# JoystickWing.net
KiCad netlist of a schematic drawn in EAGLE
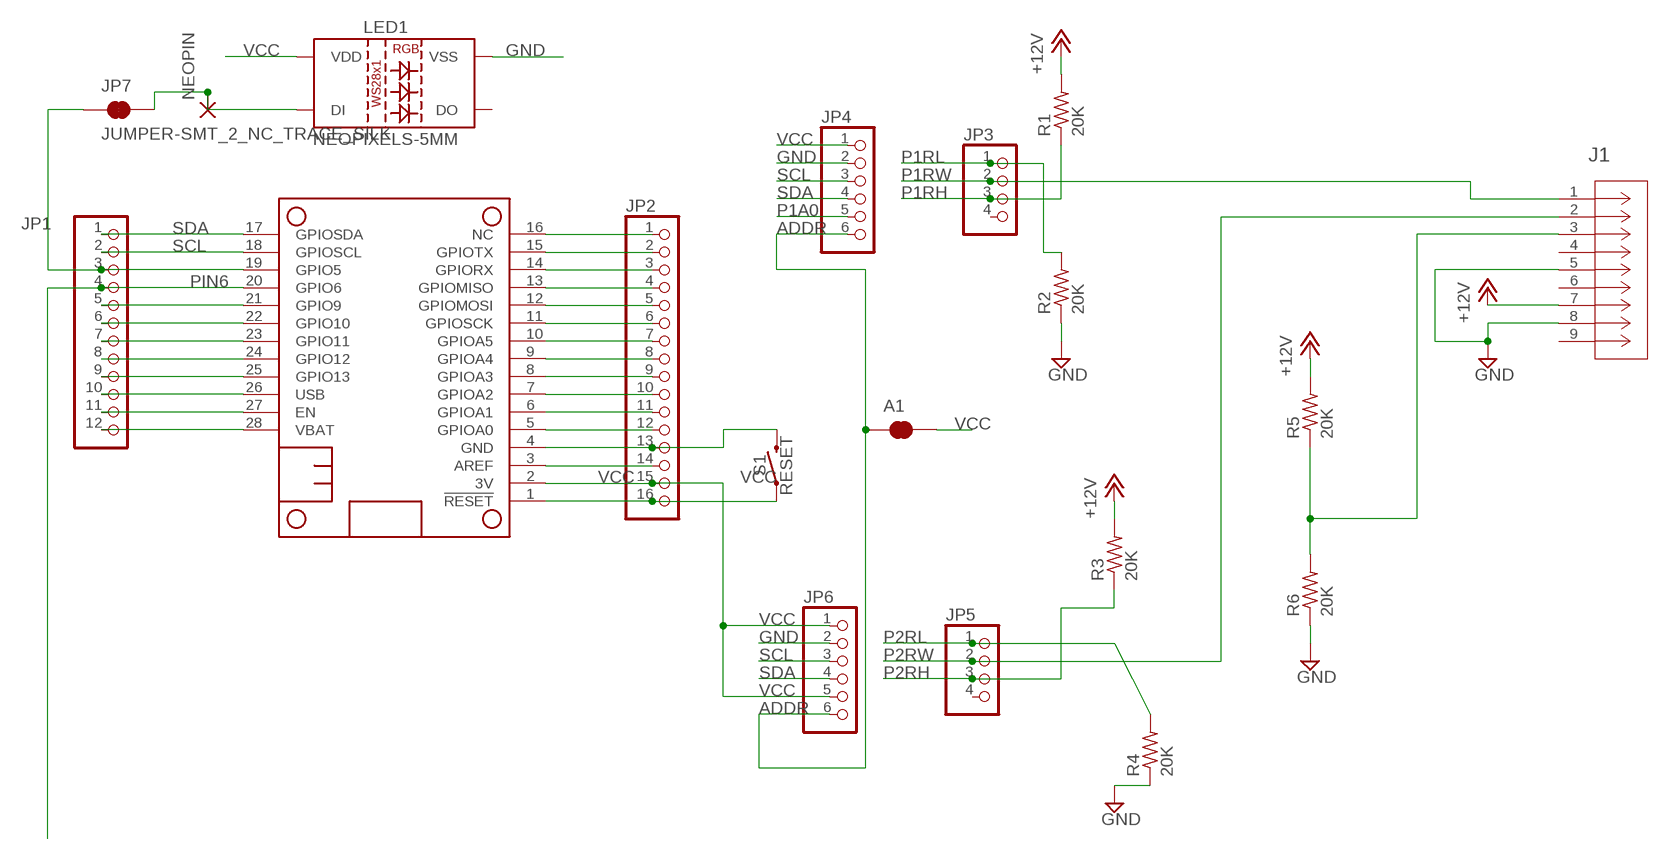
[diagram p0: schematic, sheet 1]

(export (version "E")
  (design (tool "Eeschema 10.0.6"))
  (components
    (comp (ref "A1")
      (value "JUMPER-SMT_2_NC_TRACE_SILK")
      (footprint "eagle-import:SMT-JUMPER_2_NC_TRACE_SILK")
      (libsource (lib "eagle-import") (part "JUMPER-SMT_2_NC_TRACE_SILK"))
    )
    (comp (ref "J1")
      (value "5747844-4")
      (footprint "eagle-import:CONN_5747844-4")
      (fields (field (name "MANUFACTURER_PART_NUMBER") "57478444"))
      (libsource (lib "eagle-import") (part "5747844-4"))
    )
    (comp (ref "JP1")
      (value "PINHD-1X12")
      (footprint "eagle-import:1X12")
      (libsource (lib "eagle-import") (part "PINHD-1X12"))
    )
    (comp (ref "JP2")
      (value "PINHD-1X16")
      (footprint "eagle-import:1X16")
      (libsource (lib "eagle-import") (part "PINHD-1X16"))
    )
    (comp (ref "JP3")
      (value "HEADER-1X4ROUND")
      (footprint "eagle-import:1X04_ROUND")
      (libsource (lib "eagle-import") (part "HEADER-1X4ROUND"))
    )
    (comp (ref "JP4")
      (value "HEADER-1X6ROUND")
      (footprint "eagle-import:1X06_ROUND")
      (libsource (lib "eagle-import") (part "HEADER-1X6ROUND"))
    )
    (comp (ref "JP5")
      (value "HEADER-1X4ROUND")
      (footprint "eagle-import:1X04_ROUND")
      (libsource (lib "eagle-import") (part "HEADER-1X4ROUND"))
    )
    (comp (ref "JP6")
      (value "HEADER-1X6ROUND")
      (footprint "eagle-import:1X06_ROUND")
      (libsource (lib "eagle-import") (part "HEADER-1X6ROUND"))
    )
    (comp (ref "JP7")
      (value "JUMPER-SMT_2_NC_TRACE_SILK")
      (footprint "eagle-import:SMT-JUMPER_2_NC_TRACE_SILK")
      (libsource (lib "eagle-import") (part "JUMPER-SMT_2_NC_TRACE_SILK"))
    )
    (comp (ref "LED1")
      (value "NEOPIXELS-5MM")
      (footprint "eagle-import:NEOPIXELS-5MM")
      (libsource (lib "eagle-import") (part "NEOPIXELS-5MM"))
    )
    (comp (ref "MS1")
      (value "FEATHERWING_NODIM")
      (footprint "eagle-import:FEATHERWING_DIM")
      (libsource (lib "eagle-import") (part "FEATHERWING_NODIM"))
    )
    (comp (ref "NEOPIN")
      (value "2,54/1,1")
      (footprint "eagle-import:2,54_1,1")
      (libsource (lib "eagle-import") (part "2,54/1,1"))
    )
    (comp (ref "R1")
      (value "20K")
      (footprint "eagle-import:0204_7")
      (libsource (lib "eagle-import") (part "R-US_0204/7"))
    )
    (comp (ref "R2")
      (value "20K")
      (footprint "eagle-import:0204_7")
      (libsource (lib "eagle-import") (part "R-US_0204/7"))
    )
    (comp (ref "R3")
      (value "20K")
      (footprint "eagle-import:0204_7")
      (libsource (lib "eagle-import") (part "R-US_0204/7"))
    )
    (comp (ref "R4")
      (value "20K")
      (footprint "eagle-import:0204_7")
      (libsource (lib "eagle-import") (part "R-US_0204/7"))
    )
    (comp (ref "R5")
      (value "20K")
      (footprint "eagle-import:0204_7")
      (libsource (lib "eagle-import") (part "R-US_0204/7"))
    )
    (comp (ref "R6")
      (value "20K")
      (footprint "eagle-import:0204_7")
      (libsource (lib "eagle-import") (part "R-US_0204/7"))
    )
    (comp (ref "S1")
      (value "RESET")
      (footprint "eagle-import:DTS-3")
      (libsource (lib "eagle-import") (part "SWITCH_DTS-3"))
    )
  )
  (nets
    (net (code "1") (name "+12V") (class "Default")
      (node (ref "J1") (pin "7") (pinfunction "7_7") (pintype "passive"))
      (node (ref "R1") (pin "2") (pinfunction "2_2") (pintype "passive"))
      (node (ref "R3") (pin "2") (pinfunction "2_2") (pintype "passive"))
      (node (ref "R5") (pin "2") (pinfunction "2_2") (pintype "passive"))
    )
    (net (code "2") (name "/ADDR") (class "Default")
      (node (ref "A1") (pin "1") (pinfunction "1_1") (pintype "passive"))
      (node (ref "JP4") (pin "6") (pinfunction "6_6") (pintype "passive"))
      (node (ref "JP6") (pin "6") (pinfunction "6_6") (pintype "passive"))
    )
    (net (code "3") (name "/P1A0") (class "Default")
      (node (ref "JP4") (pin "5") (pinfunction "5_5") (pintype "passive"))
    )
    (net (code "4") (name "/P1RH") (class "Default")
      (node (ref "JP3") (pin "3") (pinfunction "3_3") (pintype "passive"))
      (node (ref "R1") (pin "1") (pinfunction "1_1") (pintype "passive"))
    )
    (net (code "5") (name "/P1RL") (class "Default")
      (node (ref "JP3") (pin "1") (pinfunction "1_1") (pintype "passive"))
      (node (ref "R2") (pin "2") (pinfunction "2_2") (pintype "passive"))
    )
    (net (code "6") (name "/P1RW") (class "Default")
      (node (ref "J1") (pin "1") (pinfunction "1_1") (pintype "passive"))
      (node (ref "JP3") (pin "2") (pinfunction "2_2") (pintype "passive"))
    )
    (net (code "7") (name "/P2RH") (class "Default")
      (node (ref "JP5") (pin "3") (pinfunction "3_3") (pintype "passive"))
      (node (ref "R3") (pin "1") (pinfunction "1_1") (pintype "passive"))
    )
    (net (code "8") (name "/P2RL") (class "Default")
      (node (ref "JP5") (pin "1") (pinfunction "1_1") (pintype "passive"))
      (node (ref "R4") (pin "2") (pinfunction "2_2") (pintype "passive"))
    )
    (net (code "9") (name "/P2RW") (class "Default")
      (node (ref "J1") (pin "2") (pinfunction "2_2") (pintype "passive"))
      (node (ref "JP5") (pin "2") (pinfunction "2_2") (pintype "passive"))
    )
    (net (code "10") (name "/PIN6") (class "Default")
      (node (ref "JP1") (pin "4") (pinfunction "4_4") (pintype "passive"))
      (node (ref "MS1") (pin "20") (pinfunction "GPIO6_20") (pintype "bidirectional"))
    )
    (net (code "11") (name "/SCL") (class "Default")
      (node (ref "JP1") (pin "2") (pinfunction "2_2") (pintype "passive"))
      (node (ref "JP4") (pin "3") (pinfunction "3_3") (pintype "passive"))
      (node (ref "JP6") (pin "3") (pinfunction "3_3") (pintype "passive"))
      (node (ref "MS1") (pin "18") (pinfunction "GPIOSCL_18") (pintype "bidirectional"))
    )
    (net (code "12") (name "/SDA") (class "Default")
      (node (ref "JP1") (pin "1") (pinfunction "1_1") (pintype "passive"))
      (node (ref "JP4") (pin "4") (pinfunction "4_4") (pintype "passive"))
      (node (ref "JP6") (pin "4") (pinfunction "4_4") (pintype "passive"))
      (node (ref "MS1") (pin "17") (pinfunction "GPIOSDA_17") (pintype "bidirectional"))
    )
    (net (code "13") (name "/VCC") (class "Default")
      (node (ref "A1") (pin "2") (pinfunction "2_2") (pintype "passive"))
      (node (ref "JP2") (pin "15") (pinfunction "15_15") (pintype "passive"))
      (node (ref "JP4") (pin "1") (pinfunction "1_1") (pintype "passive"))
      (node (ref "JP6") (pin "1") (pinfunction "1_1") (pintype "passive"))
      (node (ref "JP6") (pin "5") (pinfunction "5_5") (pintype "passive"))
      (node (ref "LED1") (pin "P2") (pinfunction "VDD_P2") (pintype "bidirectional"))
      (node (ref "MS1") (pin "2") (pinfunction "3V_2") (pintype "power_in"))
    )
    (net (code "14") (name "GND") (class "Default")
      (node (ref "J1") (pin "5") (pinfunction "5_5") (pintype "passive"))
      (node (ref "J1") (pin "8") (pinfunction "8_8") (pintype "passive"))
      (node (ref "JP2") (pin "13") (pinfunction "13_13") (pintype "passive"))
      (node (ref "JP4") (pin "2") (pinfunction "2_2") (pintype "passive"))
      (node (ref "JP6") (pin "2") (pinfunction "2_2") (pintype "passive"))
      (node (ref "LED1") (pin "P3") (pinfunction "VSS_P3") (pintype "bidirectional"))
      (node (ref "MS1") (pin "4") (pinfunction "GND_4") (pintype "power_in"))
      (node (ref "R2") (pin "1") (pinfunction "1_1") (pintype "passive"))
      (node (ref "R4") (pin "1") (pinfunction "1_1") (pintype "passive"))
      (node (ref "R6") (pin "1") (pinfunction "1_1") (pintype "passive"))
      (node (ref "S1") (pin "2") (pinfunction "2_2") (pintype "passive"))
    )
    (net (code "15") (name "Net-(J1-Pad3)") (class "Default")
      (node (ref "J1") (pin "3") (pinfunction "3_3") (pintype "passive"))
      (node (ref "R5") (pin "1") (pinfunction "1_1") (pintype "passive"))
      (node (ref "R6") (pin "2") (pinfunction "2_2") (pintype "passive"))
    )
    (net (code "16") (name "Net-(LED1-DI)") (class "Default")
      (node (ref "JP7") (pin "2") (pinfunction "2_2") (pintype "passive"))
      (node (ref "LED1") (pin "P1") (pinfunction "DI_P1") (pintype "bidirectional"))
      (node (ref "NEOPIN") (pin "1") (pinfunction "P_1") (pintype "passive"))
    )
    (net (code "17") (name "Net-(MS1-AREF)") (class "Default")
      (node (ref "JP2") (pin "14") (pinfunction "14_14") (pintype "passive"))
      (node (ref "MS1") (pin "3") (pinfunction "AREF_3") (pintype "passive"))
    )
    (net (code "18") (name "Net-(MS1-EN)") (class "Default")
      (node (ref "JP1") (pin "11") (pinfunction "11_11") (pintype "passive"))
      (node (ref "MS1") (pin "27") (pinfunction "EN_27") (pintype "passive"))
    )
    (net (code "19") (name "Net-(MS1-GPIO5)") (class "Default")
      (node (ref "JP1") (pin "3") (pinfunction "3_3") (pintype "passive"))
      (node (ref "JP7") (pin "1") (pinfunction "1_1") (pintype "passive"))
      (node (ref "MS1") (pin "19") (pinfunction "GPIO5_19") (pintype "bidirectional"))
    )
    (net (code "20") (name "Net-(MS1-GPIO9)") (class "Default")
      (node (ref "JP1") (pin "5") (pinfunction "5_5") (pintype "passive"))
      (node (ref "MS1") (pin "21") (pinfunction "GPIO9_21") (pintype "bidirectional"))
    )
    (net (code "21") (name "Net-(MS1-GPIO10)") (class "Default")
      (node (ref "JP1") (pin "6") (pinfunction "6_6") (pintype "passive"))
      (node (ref "MS1") (pin "22") (pinfunction "GPIO10_22") (pintype "bidirectional"))
    )
    (net (code "22") (name "Net-(MS1-GPIO11)") (class "Default")
      (node (ref "JP1") (pin "7") (pinfunction "7_7") (pintype "passive"))
      (node (ref "MS1") (pin "23") (pinfunction "GPIO11_23") (pintype "bidirectional"))
    )
    (net (code "23") (name "Net-(MS1-GPIO12)") (class "Default")
      (node (ref "JP1") (pin "8") (pinfunction "8_8") (pintype "passive"))
      (node (ref "MS1") (pin "24") (pinfunction "GPIO12_24") (pintype "bidirectional"))
    )
    (net (code "24") (name "Net-(MS1-GPIO13)") (class "Default")
      (node (ref "JP1") (pin "9") (pinfunction "9_9") (pintype "passive"))
      (node (ref "MS1") (pin "25") (pinfunction "GPIO13_25") (pintype "bidirectional"))
    )
    (net (code "25") (name "Net-(MS1-GPIOA0)") (class "Default")
      (node (ref "JP2") (pin "12") (pinfunction "12_12") (pintype "passive"))
      (node (ref "MS1") (pin "5") (pinfunction "GPIOA0_5") (pintype "bidirectional"))
    )
    (net (code "26") (name "Net-(MS1-GPIOA1)") (class "Default")
      (node (ref "JP2") (pin "11") (pinfunction "11_11") (pintype "passive"))
      (node (ref "MS1") (pin "6") (pinfunction "GPIOA1_6") (pintype "bidirectional"))
    )
    (net (code "27") (name "Net-(MS1-GPIOA2)") (class "Default")
      (node (ref "JP2") (pin "10") (pinfunction "10_10") (pintype "passive"))
      (node (ref "MS1") (pin "7") (pinfunction "GPIOA2_7") (pintype "bidirectional"))
    )
    (net (code "28") (name "Net-(MS1-GPIOA3)") (class "Default")
      (node (ref "JP2") (pin "9") (pinfunction "9_9") (pintype "passive"))
      (node (ref "MS1") (pin "8") (pinfunction "GPIOA3_8") (pintype "bidirectional"))
    )
    (net (code "29") (name "Net-(MS1-GPIOA4)") (class "Default")
      (node (ref "JP2") (pin "8") (pinfunction "8_8") (pintype "passive"))
      (node (ref "MS1") (pin "9") (pinfunction "GPIOA4_9") (pintype "bidirectional"))
    )
    (net (code "30") (name "Net-(MS1-GPIOA5)") (class "Default")
      (node (ref "JP2") (pin "7") (pinfunction "7_7") (pintype "passive"))
      (node (ref "MS1") (pin "10") (pinfunction "GPIOA5_10") (pintype "bidirectional"))
    )
    (net (code "31") (name "Net-(MS1-GPIOMISO)") (class "Default")
      (node (ref "JP2") (pin "4") (pinfunction "4_4") (pintype "passive"))
      (node (ref "MS1") (pin "13") (pinfunction "GPIOMISO_13") (pintype "bidirectional"))
    )
    (net (code "32") (name "Net-(MS1-GPIOMOSI)") (class "Default")
      (node (ref "JP2") (pin "5") (pinfunction "5_5") (pintype "passive"))
      (node (ref "MS1") (pin "12") (pinfunction "GPIOMOSI_12") (pintype "bidirectional"))
    )
    (net (code "33") (name "Net-(MS1-GPIORX)") (class "Default")
      (node (ref "JP2") (pin "3") (pinfunction "3_3") (pintype "passive"))
      (node (ref "MS1") (pin "14") (pinfunction "GPIORX_14") (pintype "bidirectional"))
    )
    (net (code "34") (name "Net-(MS1-GPIOSCK)") (class "Default")
      (node (ref "JP2") (pin "6") (pinfunction "6_6") (pintype "passive"))
      (node (ref "MS1") (pin "11") (pinfunction "GPIOSCK_11") (pintype "bidirectional"))
    )
    (net (code "35") (name "Net-(MS1-GPIOTX)") (class "Default")
      (node (ref "JP2") (pin "2") (pinfunction "2_2") (pintype "passive"))
      (node (ref "MS1") (pin "15") (pinfunction "GPIOTX_15") (pintype "bidirectional"))
    )
    (net (code "36") (name "Net-(MS1-NC)") (class "Default")
      (node (ref "JP2") (pin "1") (pinfunction "1_1") (pintype "passive"))
      (node (ref "MS1") (pin "16") (pinfunction "NC_16") (pintype "passive"))
    )
    (net (code "37") (name "Net-(MS1-USB)") (class "Default")
      (node (ref "JP1") (pin "10") (pinfunction "10_10") (pintype "passive"))
      (node (ref "MS1") (pin "26") (pinfunction "USB_26") (pintype "power_in"))
    )
    (net (code "38") (name "Net-(MS1-VBAT)") (class "Default")
      (node (ref "JP1") (pin "12") (pinfunction "12_12") (pintype "passive"))
      (node (ref "MS1") (pin "28") (pinfunction "VBAT_28") (pintype "power_in"))
    )
    (net (code "39") (name "Net-(MS1-~{RESET})") (class "Default")
      (node (ref "JP2") (pin "16") (pinfunction "16_16") (pintype "passive"))
      (node (ref "MS1") (pin "1") (pinfunction "~{RESET}_1") (pintype "input"))
      (node (ref "S1") (pin "1") (pinfunction "1_1") (pintype "passive"))
    )
    (net (code "40") (name "unconnected-(J1-Pad4)") (class "Default")
      (node (ref "J1") (pin "4") (pinfunction "4_4") (pintype "passive"))
    )
    (net (code "41") (name "unconnected-(J1-Pad6)") (class "Default")
      (node (ref "J1") (pin "6") (pinfunction "6_6") (pintype "passive"))
    )
    (net (code "42") (name "unconnected-(J1-Pad9)") (class "Default")
      (node (ref "J1") (pin "9") (pinfunction "9_9") (pintype "passive"))
    )
    (net (code "43") (name "unconnected-(JP3-Pad4)") (class "Default")
      (node (ref "JP3") (pin "4") (pinfunction "4_4") (pintype "passive"))
    )
    (net (code "44") (name "unconnected-(JP5-Pad4)") (class "Default")
      (node (ref "JP5") (pin "4") (pinfunction "4_4") (pintype "passive"))
    )
    (net (code "45") (name "unconnected-(LED1-DO-PadP4)") (class "Default")
      (node (ref "LED1") (pin "P4") (pinfunction "DO_P4") (pintype "bidirectional"))
    )
  )
)
